# fri3d_badge_2016.net
KiCad netlist of a schematic drawn in EAGLE
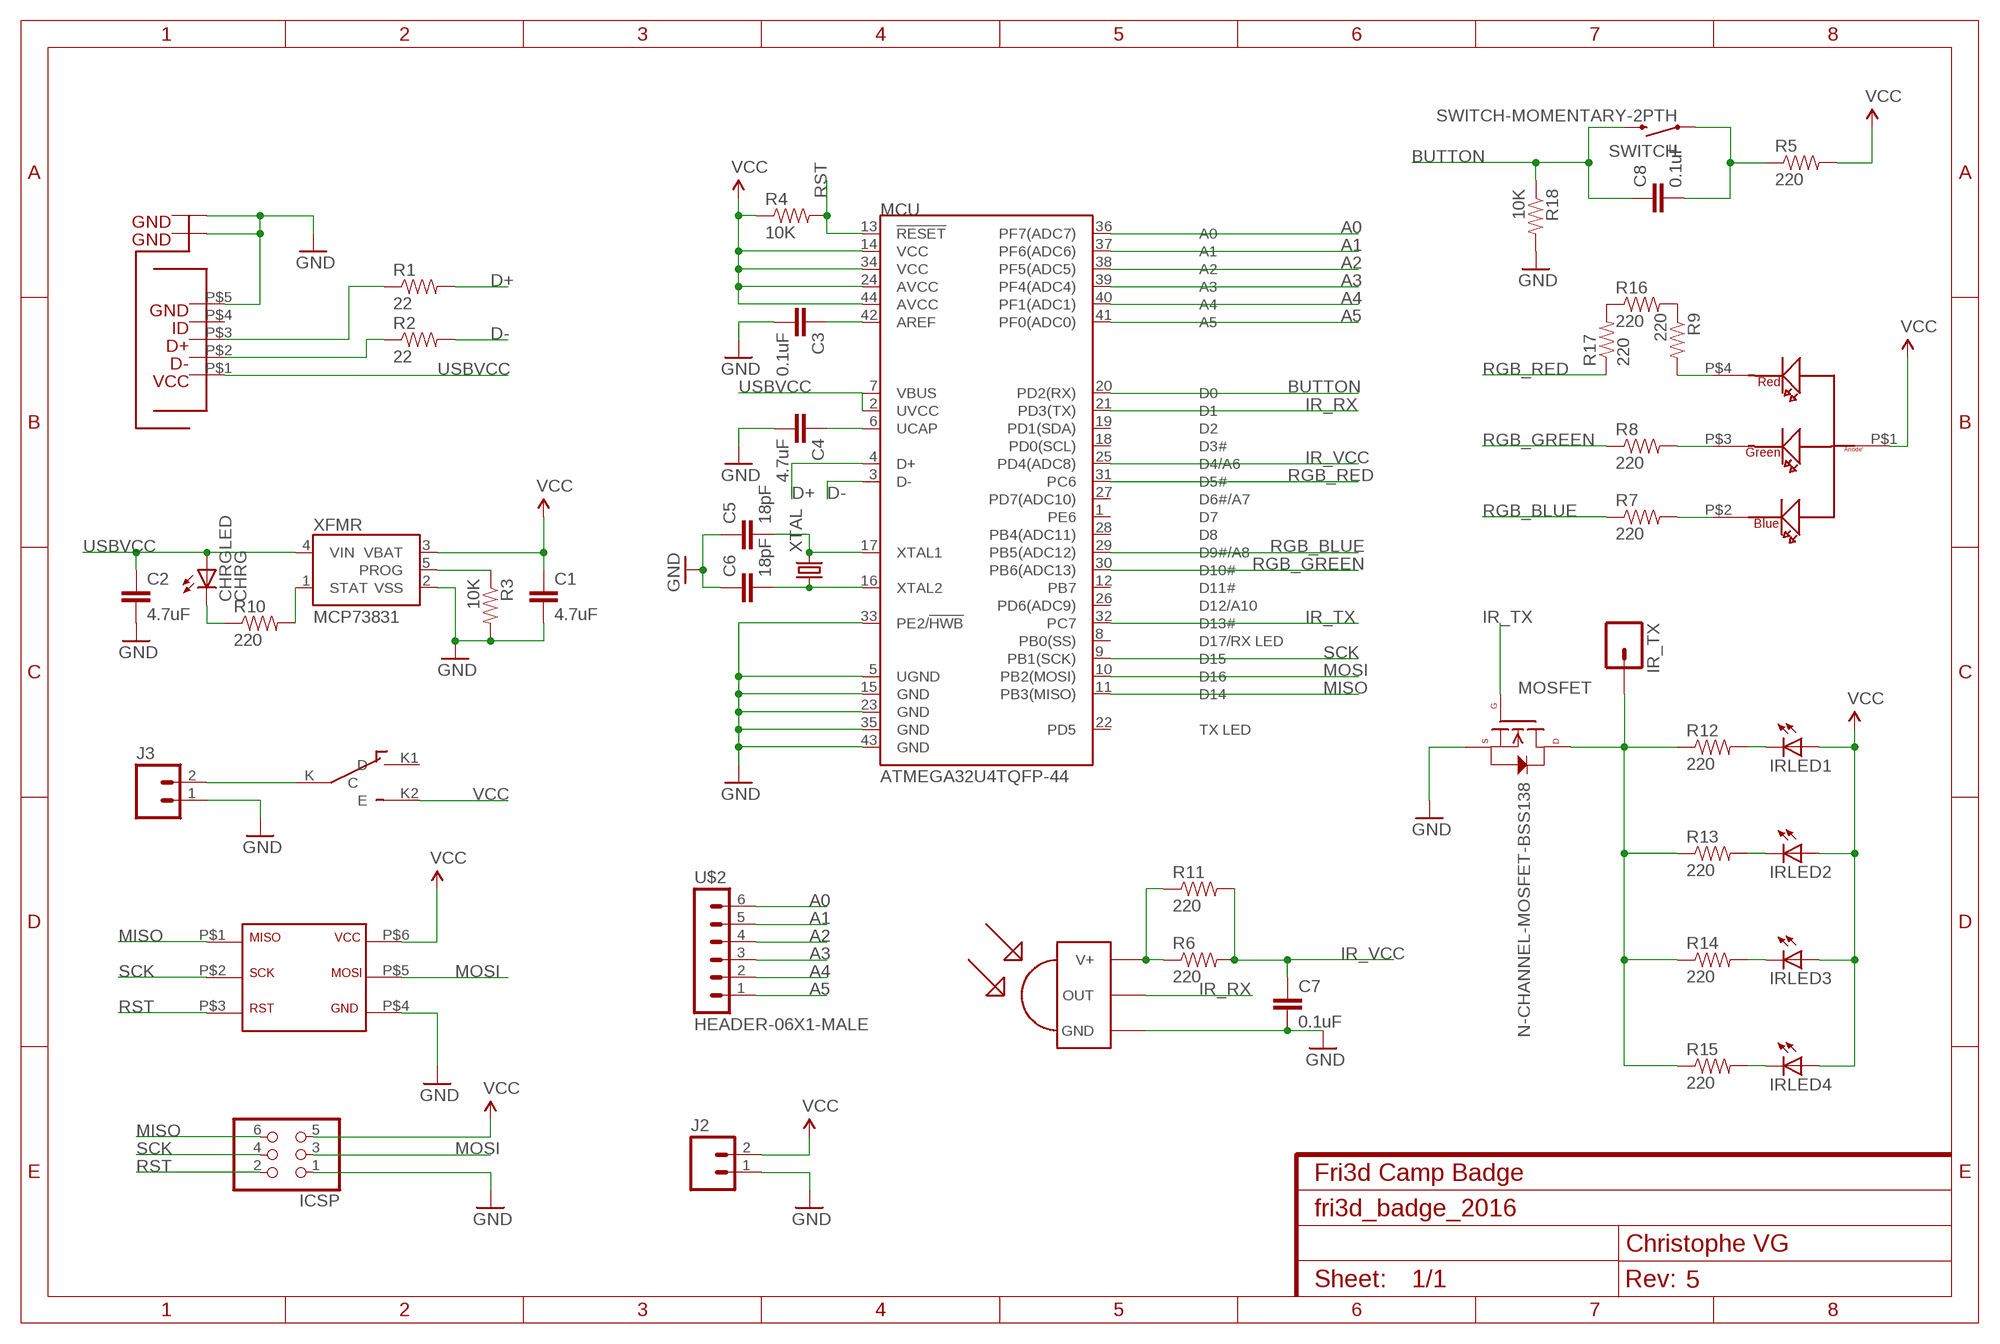
[diagram p0: schematic, sheet 1]

(export (version "E")
  (design (tool "Eeschema 10.0.6"))
  (components
    (comp (ref "C1")
      (value "4.7uF")
      (footprint "eagle-import:0805")
      (libsource (lib "eagle-import") (part "CAP0805"))
    )
    (comp (ref "C2")
      (value "4.7uF")
      (footprint "eagle-import:0805")
      (libsource (lib "eagle-import") (part "CAP0805"))
    )
    (comp (ref "C3")
      (value "0.1uF")
      (footprint "eagle-import:0805")
      (libsource (lib "eagle-import") (part "CAP0805"))
    )
    (comp (ref "C4")
      (value "4.7uF")
      (footprint "eagle-import:0805")
      (libsource (lib "eagle-import") (part "CAP0805"))
    )
    (comp (ref "C5")
      (value "18pF")
      (footprint "eagle-import:0805")
      (libsource (lib "eagle-import") (part "CAP0805"))
    )
    (comp (ref "C6")
      (value "18pF")
      (footprint "eagle-import:0805")
      (libsource (lib "eagle-import") (part "CAP0805"))
    )
    (comp (ref "C7")
      (value "0.1uF")
      (footprint "eagle-import:0805")
      (libsource (lib "eagle-import") (part "CAP0805"))
    )
    (comp (ref "C8")
      (value "0.1uF")
      (footprint "eagle-import:0805")
      (libsource (lib "eagle-import") (part "CAP0805"))
    )
    (comp (ref "CHRGLED")
      (value "CHRG")
      (footprint "eagle-import:CHIPLED_0805")
      (libsource (lib "eagle-import") (part "LEDCHIPLED_0805"))
    )
    (comp (ref "ICSP")
      (value "PINHD-2X3")
      (footprint "eagle-import:2X03")
      (libsource (lib "eagle-import") (part "PINHD-2X3"))
    )
    (comp (ref "IRLED1")
      (value "LEDCHIPLED_0805")
      (footprint "eagle-import:CHIPLED_0805")
      (libsource (lib "eagle-import") (part "led_LEDCHIPLED_0805"))
    )
    (comp (ref "IRLED2")
      (value "LEDCHIPLED_0805")
      (footprint "eagle-import:CHIPLED_0805")
      (libsource (lib "eagle-import") (part "led_LEDCHIPLED_0805"))
    )
    (comp (ref "IRLED3")
      (value "LEDCHIPLED_0805")
      (footprint "eagle-import:CHIPLED_0805")
      (libsource (lib "eagle-import") (part "led_LEDCHIPLED_0805"))
    )
    (comp (ref "IRLED4")
      (value "LEDCHIPLED_0805")
      (footprint "eagle-import:CHIPLED_0805")
      (libsource (lib "eagle-import") (part "led_LEDCHIPLED_0805"))
    )
    (comp (ref "IR_TX")
      (value "M01PTH")
      (footprint "eagle-import:1X01")
      (libsource (lib "eagle-import") (part "M01PTH"))
    )
    (comp (ref "J2")
      (value "M02PTH")
      (footprint "eagle-import:1X02")
      (libsource (lib "eagle-import") (part "M02PTH"))
    )
    (comp (ref "J3")
      (value "M02JST-PTH-2")
      (footprint "eagle-import:JST-2-PTH")
      (libsource (lib "eagle-import") (part "M02JST-PTH-2"))
    )
    (comp (ref "MCU")
      (value "ATMEGA32U4TQFP-44")
      (footprint "eagle-import:TQFP44")
      (libsource (lib "eagle-import") (part "ATMEGA32U4TQFP-44"))
    )
    (comp (ref "MOSFET")
      (value "N-CHANNEL-MOSFET-BSS138")
      (footprint "eagle-import:SOT23-3")
      (libsource (lib "eagle-import") (part "N-CHANNEL-MOSFET-BSS138"))
    )
    (comp (ref "R1")
      (value "22")
      (footprint "eagle-import:0805")
      (libsource (lib "eagle-import") (part "RESISTOR0805-RES"))
    )
    (comp (ref "R2")
      (value "22")
      (footprint "eagle-import:0805")
      (libsource (lib "eagle-import") (part "RESISTOR0805-RES"))
    )
    (comp (ref "R3")
      (value "10K")
      (footprint "eagle-import:0805")
      (libsource (lib "eagle-import") (part "RESISTOR0805-RES"))
    )
    (comp (ref "R4")
      (value "10K")
      (footprint "eagle-import:0805")
      (libsource (lib "eagle-import") (part "RESISTOR0805-RES"))
    )
    (comp (ref "R5")
      (value "220")
      (footprint "eagle-import:0805")
      (libsource (lib "eagle-import") (part "RESISTOR0805-RES"))
    )
    (comp (ref "R6")
      (value "220")
      (footprint "eagle-import:0805")
      (libsource (lib "eagle-import") (part "RESISTOR0805-RES"))
    )
    (comp (ref "R7")
      (value "220")
      (footprint "eagle-import:0805")
      (libsource (lib "eagle-import") (part "RESISTOR0805-RES"))
    )
    (comp (ref "R8")
      (value "220")
      (footprint "eagle-import:0805")
      (libsource (lib "eagle-import") (part "RESISTOR0805-RES"))
    )
    (comp (ref "R9")
      (value "220")
      (footprint "eagle-import:0805")
      (libsource (lib "eagle-import") (part "RESISTOR0805-RES"))
    )
    (comp (ref "R10")
      (value "220")
      (footprint "eagle-import:0805")
      (libsource (lib "eagle-import") (part "RESISTOR0805-RES"))
    )
    (comp (ref "R11")
      (value "220")
      (footprint "eagle-import:0805")
      (libsource (lib "eagle-import") (part "RESISTOR0805-RES"))
    )
    (comp (ref "R12")
      (value "220")
      (footprint "eagle-import:0805")
      (libsource (lib "eagle-import") (part "RESISTOR0805-RES"))
    )
    (comp (ref "R13")
      (value "220")
      (footprint "eagle-import:0805")
      (libsource (lib "eagle-import") (part "RESISTOR0805-RES"))
    )
    (comp (ref "R14")
      (value "220")
      (footprint "eagle-import:0805")
      (libsource (lib "eagle-import") (part "RESISTOR0805-RES"))
    )
    (comp (ref "R15")
      (value "220")
      (footprint "eagle-import:0805")
      (libsource (lib "eagle-import") (part "RESISTOR0805-RES"))
    )
    (comp (ref "R16")
      (value "220")
      (footprint "eagle-import:0805")
      (libsource (lib "eagle-import") (part "RESISTOR0805-RES"))
    )
    (comp (ref "R17")
      (value "220")
      (footprint "eagle-import:0805")
      (libsource (lib "eagle-import") (part "RESISTOR0805-RES"))
    )
    (comp (ref "R18")
      (value "10K")
      (footprint "eagle-import:0805")
      (libsource (lib "eagle-import") (part "RESISTOR0805-RES"))
    )
    (comp (ref "SWITCH")
      (value "SWITCH-MOMENTARY-2PTH")
      (footprint "eagle-import:TACTILE-PTH")
      (libsource (lib "eagle-import") (part "SWITCH-MOMENTARY-2PTH"))
    )
    (comp (ref "U$2")
      (value "HEADER-06X1-MALE")
      (footprint "eagle-import:06X1-PTH")
      (libsource (lib "eagle-import") (part "HEADER-06X1?-MALE"))
    )
    (comp (ref "U$3")
      (value "TSOP4838")
      (footprint "eagle-import:TSOP18XX")
      (libsource (lib "eagle-import") (part "TSOP4838"))
    )
    (comp (ref "U$4")
      (value "DRAGAN-PERSONAL_AVAGO-RGB-LED")
      (footprint "eagle-import:DRAGAN-PERSONAL_AVAGO-RGB-LED")
      (libsource (lib "eagle-import") (part "DRAGAN-PERSONAL_AVAGO-RGB-LED"))
    )
    (comp (ref "U$5")
      (value "OCTA-CORE_MCIRO-USB2MOUSER")
      (footprint "eagle-import:OCTA-CORE_MICRO-USB2")
      (libsource (lib "eagle-import") (part "OCTA-CORE_MCIRO-USB2MOUSER"))
    )
    (comp (ref "U$6")
      (value "SLIDE-SWITCH")
      (footprint "eagle-import:SLIDE-SWITCH")
      (libsource (lib "eagle-import") (part "SLIDE-SWITCH"))
    )
    (comp (ref "U$7")
      (value "OCTA-CORE_TC2030-IDC")
      (footprint "eagle-import:OCTA-CORE_TC2030-IDC")
      (libsource (lib "eagle-import") (part "OCTA-CORE_TC2030-IDC"))
    )
    (comp (ref "XFMR")
      (value "MCP73831")
      (footprint "eagle-import:SOT23-5")
      (libsource (lib "eagle-import") (part "MCP73831"))
    )
    (comp (ref "XTAL")
      (value "CRYSTALHC49S")
      (footprint "eagle-import:HC49_S")
      (libsource (lib "eagle-import") (part "CRYSTALHC49S"))
    )
  )
  (nets
    (net (code "1") (name "/A0") (class "Default")
      (node (ref "MCU") (pin "36") (pinfunction "PF7(ADC7)_36") (pintype "bidirectional"))
      (node (ref "U$2") (pin "6") (pinfunction "6_6") (pintype "passive"))
    )
    (net (code "2") (name "/A1") (class "Default")
      (node (ref "MCU") (pin "37") (pinfunction "PF6(ADC6)_37") (pintype "bidirectional"))
      (node (ref "U$2") (pin "5") (pinfunction "5_5") (pintype "passive"))
    )
    (net (code "3") (name "/A2") (class "Default")
      (node (ref "MCU") (pin "38") (pinfunction "PF5(ADC5)_38") (pintype "bidirectional"))
      (node (ref "U$2") (pin "4") (pinfunction "4_4") (pintype "passive"))
    )
    (net (code "4") (name "/A3") (class "Default")
      (node (ref "MCU") (pin "39") (pinfunction "PF4(ADC4)_39") (pintype "bidirectional"))
      (node (ref "U$2") (pin "3") (pinfunction "3_3") (pintype "passive"))
    )
    (net (code "5") (name "/A4") (class "Default")
      (node (ref "MCU") (pin "40") (pinfunction "PF1(ADC1)_40") (pintype "bidirectional"))
      (node (ref "U$2") (pin "2") (pinfunction "2_2") (pintype "passive"))
    )
    (net (code "6") (name "/A5") (class "Default")
      (node (ref "MCU") (pin "41") (pinfunction "PF0(ADC0)_41") (pintype "bidirectional"))
      (node (ref "U$2") (pin "1") (pinfunction "1_1") (pintype "passive"))
    )
    (net (code "7") (name "/BUTTON") (class "Default")
      (node (ref "C8") (pin "1") (pinfunction "1_1") (pintype "passive"))
      (node (ref "MCU") (pin "20") (pinfunction "PD2(RX)_20") (pintype "bidirectional"))
      (node (ref "R18") (pin "1") (pinfunction "1_1") (pintype "passive"))
      (node (ref "SWITCH") (pin "3") (pinfunction "2_3") (pintype "passive"))
    )
    (net (code "8") (name "/D+") (class "Default")
      (node (ref "MCU") (pin "4") (pinfunction "D+_4") (pintype "bidirectional"))
      (node (ref "R1") (pin "2") (pinfunction "2_2") (pintype "passive"))
    )
    (net (code "9") (name "/D-") (class "Default")
      (node (ref "MCU") (pin "3") (pinfunction "D-_3") (pintype "bidirectional"))
      (node (ref "R2") (pin "2") (pinfunction "2_2") (pintype "passive"))
    )
    (net (code "10") (name "/IR_RX") (class "Default")
      (node (ref "MCU") (pin "21") (pinfunction "PD3(TX)_21") (pintype "bidirectional"))
      (node (ref "U$3") (pin "OUT") (pinfunction "OUT_OUT") (pintype "bidirectional"))
    )
    (net (code "11") (name "/IR_TX") (class "Default")
      (node (ref "MCU") (pin "32") (pinfunction "PC7_32") (pintype "bidirectional"))
      (node (ref "MOSFET") (pin "1") (pinfunction "G_1") (pintype "passive"))
    )
    (net (code "12") (name "/IR_VCC") (class "Default")
      (node (ref "C7") (pin "1") (pinfunction "1_1") (pintype "passive"))
      (node (ref "MCU") (pin "25") (pinfunction "PD4(ADC8)_25") (pintype "bidirectional"))
      (node (ref "R11") (pin "2") (pinfunction "2_2") (pintype "passive"))
      (node (ref "R6") (pin "2") (pinfunction "2_2") (pintype "passive"))
    )
    (net (code "13") (name "/MISO") (class "Default")
      (node (ref "ICSP") (pin "6") (pinfunction "6_6") (pintype "passive"))
      (node (ref "MCU") (pin "11") (pinfunction "PB3(MISO)_11") (pintype "bidirectional"))
      (node (ref "U$7") (pin "P$1") (pinfunction "P$1_P$1") (pintype "bidirectional"))
    )
    (net (code "14") (name "/MOSI") (class "Default")
      (node (ref "ICSP") (pin "3") (pinfunction "3_3") (pintype "passive"))
      (node (ref "MCU") (pin "10") (pinfunction "PB2(MOSI)_10") (pintype "bidirectional"))
      (node (ref "U$7") (pin "P$5") (pinfunction "P$5_P$5") (pintype "bidirectional"))
    )
    (net (code "15") (name "/RGB_BLUE") (class "Default")
      (node (ref "MCU") (pin "29") (pinfunction "PB5(ADC12)_29") (pintype "bidirectional"))
      (node (ref "R7") (pin "1") (pinfunction "1_1") (pintype "passive"))
    )
    (net (code "16") (name "/RGB_GREEN") (class "Default")
      (node (ref "MCU") (pin "30") (pinfunction "PB6(ADC13)_30") (pintype "bidirectional"))
      (node (ref "R8") (pin "1") (pinfunction "1_1") (pintype "passive"))
    )
    (net (code "17") (name "/RGB_RED") (class "Default")
      (node (ref "MCU") (pin "31") (pinfunction "PC6_31") (pintype "bidirectional"))
      (node (ref "R17") (pin "1") (pinfunction "1_1") (pintype "passive"))
    )
    (net (code "18") (name "/RST") (class "Default")
      (node (ref "ICSP") (pin "2") (pinfunction "2_2") (pintype "passive"))
      (node (ref "MCU") (pin "13") (pinfunction "~{RESET}_13") (pintype "bidirectional"))
      (node (ref "R4") (pin "2") (pinfunction "2_2") (pintype "passive"))
      (node (ref "U$7") (pin "P$3") (pinfunction "P$3_P$3") (pintype "bidirectional"))
    )
    (net (code "19") (name "/SCK") (class "Default")
      (node (ref "ICSP") (pin "4") (pinfunction "4_4") (pintype "passive"))
      (node (ref "MCU") (pin "9") (pinfunction "PB1(SCK)_9") (pintype "bidirectional"))
      (node (ref "U$7") (pin "P$2") (pinfunction "P$2_P$2") (pintype "bidirectional"))
    )
    (net (code "20") (name "/USBVCC") (class "Default")
      (node (ref "C2") (pin "1") (pinfunction "1_1") (pintype "passive"))
      (node (ref "CHRGLED") (pin "A") (pinfunction "A_A") (pintype "passive"))
      (node (ref "MCU") (pin "2") (pinfunction "UVCC_2") (pintype "bidirectional"))
      (node (ref "MCU") (pin "7") (pinfunction "VBUS_7") (pintype "bidirectional"))
      (node (ref "U$5") (pin "P$1") (pinfunction "P$1_P$1") (pintype "bidirectional"))
      (node (ref "XFMR") (pin "4") (pinfunction "VIN_4") (pintype "power_in"))
    )
    (net (code "21") (name "GND") (class "Default")
      (node (ref "C1") (pin "2") (pinfunction "2_2") (pintype "passive"))
      (node (ref "C2") (pin "2") (pinfunction "2_2") (pintype "passive"))
      (node (ref "C3") (pin "2") (pinfunction "2_2") (pintype "passive"))
      (node (ref "C4") (pin "2") (pinfunction "2_2") (pintype "passive"))
      (node (ref "C5") (pin "1") (pinfunction "1_1") (pintype "passive"))
      (node (ref "C6") (pin "1") (pinfunction "1_1") (pintype "passive"))
      (node (ref "C7") (pin "2") (pinfunction "2_2") (pintype "passive"))
      (node (ref "ICSP") (pin "1") (pinfunction "1_1") (pintype "passive"))
      (node (ref "J2") (pin "1") (pinfunction "1_1") (pintype "passive"))
      (node (ref "J3") (pin "1") (pinfunction "1_1") (pintype "passive"))
      (node (ref "MCU") (pin "15") (pinfunction "GND_15") (pintype "bidirectional"))
      (node (ref "MCU") (pin "23") (pinfunction "GND_23") (pintype "bidirectional"))
      (node (ref "MCU") (pin "33") (pinfunction "PE2/~{HWB}_33") (pintype "bidirectional"))
      (node (ref "MCU") (pin "35") (pinfunction "GND_35") (pintype "bidirectional"))
      (node (ref "MCU") (pin "43") (pinfunction "GND_43") (pintype "bidirectional"))
      (node (ref "MCU") (pin "5") (pinfunction "UGND_5") (pintype "bidirectional"))
      (node (ref "MOSFET") (pin "2") (pinfunction "S_2") (pintype "passive"))
      (node (ref "R18") (pin "2") (pinfunction "2_2") (pintype "passive"))
      (node (ref "R3") (pin "2") (pinfunction "2_2") (pintype "passive"))
      (node (ref "U$3") (pin "GND") (pinfunction "GND_GND") (pintype "bidirectional"))
      (node (ref "U$5") (pin "P$10") (pinfunction "P$7_P$10") (pintype "bidirectional"))
      (node (ref "U$5") (pin "P$11") (pinfunction "P$7_P$11") (pintype "bidirectional"))
      (node (ref "U$5") (pin "P$12") (pinfunction "P$6_P$12") (pintype "bidirectional"))
      (node (ref "U$5") (pin "P$13") (pinfunction "P$6_P$13") (pintype "bidirectional"))
      (node (ref "U$5") (pin "P$5") (pinfunction "P$5_P$5") (pintype "bidirectional"))
      (node (ref "U$5") (pin "P$6") (pinfunction "P$6_P$6") (pintype "bidirectional"))
      (node (ref "U$5") (pin "P$7") (pinfunction "P$6_P$7") (pintype "bidirectional"))
      (node (ref "U$5") (pin "P$8") (pinfunction "P$7_P$8") (pintype "bidirectional"))
      (node (ref "U$5") (pin "P$9") (pinfunction "P$7_P$9") (pintype "bidirectional"))
      (node (ref "U$7") (pin "P$4") (pinfunction "P$4_P$4") (pintype "bidirectional"))
      (node (ref "XFMR") (pin "2") (pinfunction "VSS_2") (pintype "power_in"))
    )
    (net (code "22") (name "Net-(C8-Pad2)") (class "Default")
      (node (ref "C8") (pin "2") (pinfunction "2_2") (pintype "passive"))
      (node (ref "R5") (pin "1") (pinfunction "1_1") (pintype "passive"))
      (node (ref "SWITCH") (pin "1") (pinfunction "1_1") (pintype "passive"))
    )
    (net (code "23") (name "Net-(CHRGLED-PadC)") (class "Default")
      (node (ref "CHRGLED") (pin "C") (pinfunction "C_C") (pintype "passive"))
      (node (ref "R10") (pin "1") (pinfunction "1_1") (pintype "passive"))
    )
    (net (code "24") (name "Net-(IRLED1-PadC)") (class "Default")
      (node (ref "IRLED1") (pin "C") (pinfunction "C_C") (pintype "passive"))
      (node (ref "R12") (pin "2") (pinfunction "2_2") (pintype "passive"))
    )
    (net (code "25") (name "Net-(IRLED2-PadC)") (class "Default")
      (node (ref "IRLED2") (pin "C") (pinfunction "C_C") (pintype "passive"))
      (node (ref "R13") (pin "2") (pinfunction "2_2") (pintype "passive"))
    )
    (net (code "26") (name "Net-(IRLED3-PadC)") (class "Default")
      (node (ref "IRLED3") (pin "C") (pinfunction "C_C") (pintype "passive"))
      (node (ref "R14") (pin "2") (pinfunction "2_2") (pintype "passive"))
    )
    (net (code "27") (name "Net-(IRLED4-PadC)") (class "Default")
      (node (ref "IRLED4") (pin "C") (pinfunction "C_C") (pintype "passive"))
      (node (ref "R15") (pin "2") (pinfunction "2_2") (pintype "passive"))
    )
    (net (code "28") (name "Net-(MCU-AREF)") (class "Default")
      (node (ref "C3") (pin "1") (pinfunction "1_1") (pintype "passive"))
      (node (ref "MCU") (pin "42") (pinfunction "AREF_42") (pintype "bidirectional"))
    )
    (net (code "29") (name "Net-(MCU-UCAP)") (class "Default")
      (node (ref "C4") (pin "1") (pinfunction "1_1") (pintype "passive"))
      (node (ref "MCU") (pin "6") (pinfunction "UCAP_6") (pintype "bidirectional"))
    )
    (net (code "30") (name "Net-(MCU-XTAL1)") (class "Default")
      (node (ref "C5") (pin "2") (pinfunction "2_2") (pintype "passive"))
      (node (ref "MCU") (pin "17") (pinfunction "XTAL1_17") (pintype "bidirectional"))
      (node (ref "XTAL") (pin "2") (pinfunction "2_2") (pintype "passive"))
    )
    (net (code "31") (name "Net-(MCU-XTAL2)") (class "Default")
      (node (ref "C6") (pin "2") (pinfunction "2_2") (pintype "passive"))
      (node (ref "MCU") (pin "16") (pinfunction "XTAL2_16") (pintype "bidirectional"))
      (node (ref "XTAL") (pin "1") (pinfunction "1_1") (pintype "passive"))
    )
    (net (code "32") (name "Net-(MOSFET-D)") (class "Default")
      (node (ref "IR_TX") (pin "1") (pinfunction "1_1") (pintype "passive"))
      (node (ref "MOSFET") (pin "3") (pinfunction "D_3") (pintype "passive"))
      (node (ref "R12") (pin "1") (pinfunction "1_1") (pintype "passive"))
      (node (ref "R13") (pin "1") (pinfunction "1_1") (pintype "passive"))
      (node (ref "R14") (pin "1") (pinfunction "1_1") (pintype "passive"))
      (node (ref "R15") (pin "1") (pinfunction "1_1") (pintype "passive"))
    )
    (net (code "33") (name "Net-(R1-Pad1)") (class "Default")
      (node (ref "R1") (pin "1") (pinfunction "1_1") (pintype "passive"))
      (node (ref "U$5") (pin "P$3") (pinfunction "P$3_P$3") (pintype "bidirectional"))
    )
    (net (code "34") (name "Net-(R2-Pad1)") (class "Default")
      (node (ref "R2") (pin "1") (pinfunction "1_1") (pintype "passive"))
      (node (ref "U$5") (pin "P$2") (pinfunction "P$2_P$2") (pintype "bidirectional"))
    )
    (net (code "35") (name "Net-(R7-Pad2)") (class "Default")
      (node (ref "R7") (pin "2") (pinfunction "2_2") (pintype "passive"))
      (node (ref "U$4") (pin "P$2") (pinfunction "P$2_P$2") (pintype "bidirectional"))
    )
    (net (code "36") (name "Net-(R8-Pad2)") (class "Default")
      (node (ref "R8") (pin "2") (pinfunction "2_2") (pintype "passive"))
      (node (ref "U$4") (pin "P$3") (pinfunction "P$3_P$3") (pintype "bidirectional"))
    )
    (net (code "37") (name "Net-(R9-Pad2)") (class "Default")
      (node (ref "R9") (pin "2") (pinfunction "2_2") (pintype "passive"))
      (node (ref "U$4") (pin "P$4") (pinfunction "P$4_P$4") (pintype "bidirectional"))
    )
    (net (code "38") (name "Net-(R16-Pad1)") (class "Default")
      (node (ref "R16") (pin "1") (pinfunction "1_1") (pintype "passive"))
      (node (ref "R17") (pin "2") (pinfunction "2_2") (pintype "passive"))
    )
    (net (code "39") (name "Net-(R16-Pad2)") (class "Default")
      (node (ref "R16") (pin "2") (pinfunction "2_2") (pintype "passive"))
      (node (ref "R9") (pin "1") (pinfunction "1_1") (pintype "passive"))
    )
    (net (code "40") (name "Net-(U$3-V+)") (class "Default")
      (node (ref "R11") (pin "1") (pinfunction "1_1") (pintype "passive"))
      (node (ref "R6") (pin "1") (pinfunction "1_1") (pintype "passive"))
      (node (ref "U$3") (pin "VCC") (pinfunction "V+_VCC") (pintype "bidirectional"))
    )
    (net (code "41") (name "Net-(U$6-C)") (class "Default")
      (node (ref "J3") (pin "2") (pinfunction "2_2") (pintype "passive"))
      (node (ref "U$6") (pin "K") (pinfunction "C_K") (pintype "bidirectional"))
    )
    (net (code "42") (name "Net-(XFMR-PROG)") (class "Default")
      (node (ref "R3") (pin "1") (pinfunction "1_1") (pintype "passive"))
      (node (ref "XFMR") (pin "5") (pinfunction "PROG_5") (pintype "input"))
    )
    (net (code "43") (name "Net-(XFMR-STAT)") (class "Default")
      (node (ref "R10") (pin "2") (pinfunction "2_2") (pintype "passive"))
      (node (ref "XFMR") (pin "1") (pinfunction "STAT_1") (pintype "output"))
    )
    (net (code "44") (name "VCC") (class "Default")
      (node (ref "C1") (pin "1") (pinfunction "1_1") (pintype "passive"))
      (node (ref "ICSP") (pin "5") (pinfunction "5_5") (pintype "passive"))
      (node (ref "IRLED1") (pin "A") (pinfunction "A_A") (pintype "passive"))
      (node (ref "IRLED2") (pin "A") (pinfunction "A_A") (pintype "passive"))
      (node (ref "IRLED3") (pin "A") (pinfunction "A_A") (pintype "passive"))
      (node (ref "IRLED4") (pin "A") (pinfunction "A_A") (pintype "passive"))
      (node (ref "J2") (pin "2") (pinfunction "2_2") (pintype "passive"))
      (node (ref "MCU") (pin "14") (pinfunction "VCC_14") (pintype "bidirectional"))
      (node (ref "MCU") (pin "24") (pinfunction "AVCC_24") (pintype "bidirectional"))
      (node (ref "MCU") (pin "34") (pinfunction "VCC_34") (pintype "bidirectional"))
      (node (ref "MCU") (pin "44") (pinfunction "AVCC_44") (pintype "bidirectional"))
      (node (ref "R4") (pin "1") (pinfunction "1_1") (pintype "passive"))
      (node (ref "R5") (pin "2") (pinfunction "2_2") (pintype "passive"))
      (node (ref "U$4") (pin "P$1") (pinfunction "P$1_P$1") (pintype "bidirectional"))
      (node (ref "U$6") (pin "K2") (pinfunction "E_K2") (pintype "bidirectional"))
      (node (ref "U$7") (pin "P$6") (pinfunction "P$6_P$6") (pintype "bidirectional"))
      (node (ref "XFMR") (pin "3") (pinfunction "VBAT_3") (pintype "power_in"))
    )
    (net (code "45") (name "unconnected-(MCU-PB0(SS)-Pad8)") (class "Default")
      (node (ref "MCU") (pin "8") (pinfunction "PB0(SS)_8") (pintype "bidirectional"))
    )
    (net (code "46") (name "unconnected-(MCU-PB4(ADC11)-Pad28)") (class "Default")
      (node (ref "MCU") (pin "28") (pinfunction "PB4(ADC11)_28") (pintype "bidirectional"))
    )
    (net (code "47") (name "unconnected-(MCU-PB7-Pad12)") (class "Default")
      (node (ref "MCU") (pin "12") (pinfunction "PB7_12") (pintype "bidirectional"))
    )
    (net (code "48") (name "unconnected-(MCU-PD0(SCL)-Pad18)") (class "Default")
      (node (ref "MCU") (pin "18") (pinfunction "PD0(SCL)_18") (pintype "bidirectional"))
    )
    (net (code "49") (name "unconnected-(MCU-PD1(SDA)-Pad19)") (class "Default")
      (node (ref "MCU") (pin "19") (pinfunction "PD1(SDA)_19") (pintype "bidirectional"))
    )
    (net (code "50") (name "unconnected-(MCU-PD5-Pad22)") (class "Default")
      (node (ref "MCU") (pin "22") (pinfunction "PD5_22") (pintype "bidirectional"))
    )
    (net (code "51") (name "unconnected-(MCU-PD6(ADC9)-Pad26)") (class "Default")
      (node (ref "MCU") (pin "26") (pinfunction "PD6(ADC9)_26") (pintype "bidirectional"))
    )
    (net (code "52") (name "unconnected-(MCU-PD7(ADC10)-Pad27)") (class "Default")
      (node (ref "MCU") (pin "27") (pinfunction "PD7(ADC10)_27") (pintype "bidirectional"))
    )
    (net (code "53") (name "unconnected-(MCU-PE6-Pad1)") (class "Default")
      (node (ref "MCU") (pin "1") (pinfunction "PE6_1") (pintype "bidirectional"))
    )
    (net (code "54") (name "unconnected-(U$5-PadP$4)") (class "Default")
      (node (ref "U$5") (pin "P$4") (pinfunction "P$4_P$4") (pintype "bidirectional"))
    )
    (net (code "55") (name "unconnected-(U$6-D-PadK1)") (class "Default")
      (node (ref "U$6") (pin "K1") (pinfunction "D_K1") (pintype "bidirectional"))
    )
  )
)
